# SpeakerEngine.net
KiCad netlist of a schematic drawn in Altium Designer
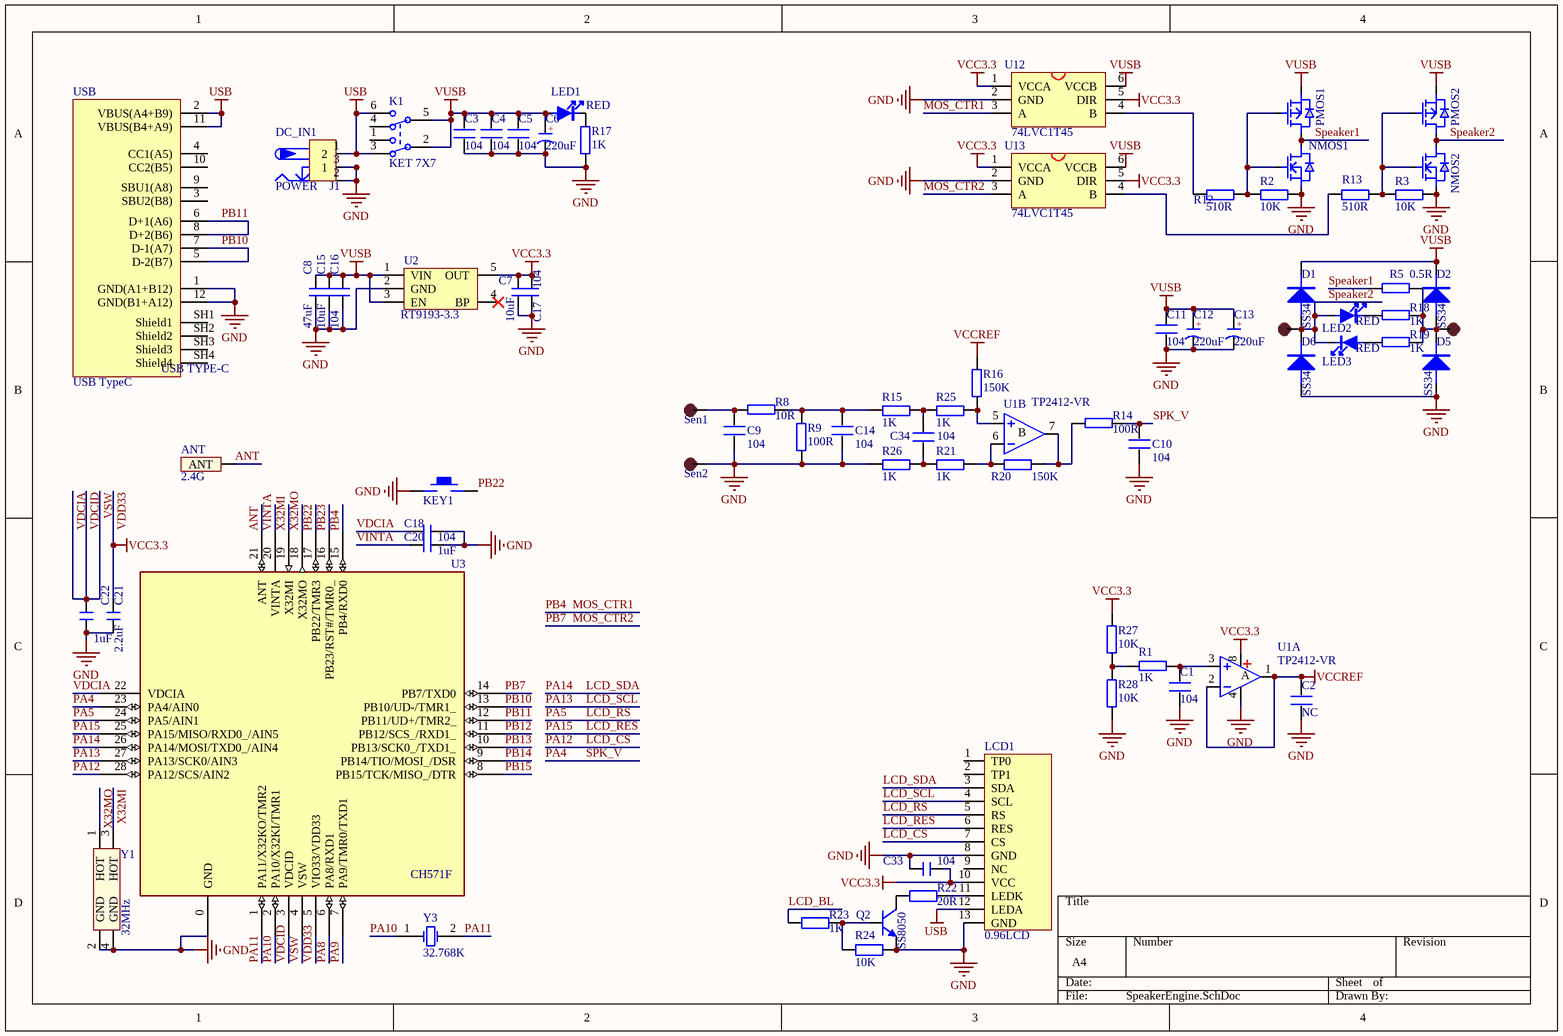
[diagram p0: SpeakerEngine.SchDoc]

(export (version "E")
  (design (tool "Eeschema 10.0.6"))
  (components
    (comp (ref "ANT")
      (value "2.4G")
      (footprint "2.4GANTS8")
      (description "2.4G天线")
      (libsource (lib "LovelessingSch") (part "ANT"))
    )
    (comp (ref "C1")
      (value "104")
      (footprint "C 0603_L")
      (libsource (lib "IMX6UL_ALPHA(底板)_V2.0") (part "C"))
    )
    (comp (ref "C2") (value "NC") (footprint "C 0603_L") (libsource (lib "IMX6UL_ALPHA(底板)_V2.0") (part "C")))
    (comp (ref "C3")
      (value "104")
      (footprint "C 0603_L")
      (libsource (lib "IMX6UL_ALPHA(底板)_V2.0") (part "C"))
    )
    (comp (ref "C4")
      (value "104")
      (footprint "C 0603_L")
      (libsource (lib "IMX6UL_ALPHA(底板)_V2.0") (part "C"))
    )
    (comp (ref "C5")
      (value "104")
      (footprint "C 0603_L")
      (libsource (lib "IMX6UL_ALPHA(底板)_V2.0") (part "C"))
    )
    (comp (ref "C6")
      (value "220uF")
      (footprint "CM D(6.3*5.4)")
      (description "有极性电容")
      (fields (field (name "版权归属") "正点原子"))
      (libsource (lib "正点原子封装库V1.0") (part "C-CAP"))
    )
    (comp (ref "C7")
      (value "10uF")
      (footprint "C 0603_L")
      (description "无极性贴片电容")
      (fields (field (name "版权归属") "正点原子"))
      (libsource (lib "电阻-电容-电感") (part "C"))
    )
    (comp (ref "C8")
      (value "47uF")
      (footprint "C 0603_L")
      (description "无极性贴片电容")
      (fields (field (name "版权归属") "正点原子"))
      (libsource (lib "电阻-电容-电感") (part "C"))
    )
    (comp (ref "C9")
      (value "104")
      (footprint "C 0603_L")
      (libsource (lib "IMX6UL_ALPHA(底板)_V2.0") (part "C"))
    )
    (comp (ref "C10")
      (value "104")
      (footprint "C 0603_L")
      (libsource (lib "IMX6UL_ALPHA(底板)_V2.0") (part "C"))
    )
    (comp (ref "C11")
      (value "104")
      (footprint "C 0603_L")
      (libsource (lib "IMX6UL_ALPHA(底板)_V2.0") (part "C"))
    )
    (comp (ref "C12")
      (value "220uF")
      (footprint "CM D(6.3*5.4)")
      (description "有极性电容")
      (fields (field (name "版权归属") "正点原子"))
      (libsource (lib "正点原子封装库V1.0") (part "C-CAP"))
    )
    (comp (ref "C13")
      (value "220uF")
      (footprint "CM D(6.3*5.4)")
      (description "有极性电容")
      (fields (field (name "版权归属") "正点原子"))
      (libsource (lib "正点原子封装库V1.0") (part "C-CAP"))
    )
    (comp (ref "C14")
      (value "104")
      (footprint "C 0603_L")
      (libsource (lib "IMX6UL_ALPHA(底板)_V2.0") (part "C"))
    )
    (comp (ref "C15")
      (value "10uF")
      (footprint "C 0603_L")
      (description "无极性贴片电容")
      (fields (field (name "版权归属") "正点原子"))
      (libsource (lib "电阻-电容-电感") (part "C"))
    )
    (comp (ref "C16")
      (value "104")
      (footprint "C 0603_L")
      (description "无极性贴片电容")
      (fields (field (name "版权归属") "正点原子"))
      (libsource (lib "电阻-电容-电感") (part "C"))
    )
    (comp (ref "C17")
      (value "104")
      (footprint "C 0603_L")
      (description "无极性贴片电容")
      (fields (field (name "版权归属") "正点原子"))
      (libsource (lib "电阻-电容-电感") (part "C"))
    )
    (comp (ref "C18")
      (value "104")
      (footprint "C 0603_L")
      (description "无极性贴片电容")
      (libsource (lib "LovelessingSch") (part "C"))
    )
    (comp (ref "C20")
      (value "1uF")
      (footprint "C 0603_L")
      (description "无极性贴片电容")
      (libsource (lib "LovelessingSch") (part "C"))
    )
    (comp (ref "C21")
      (value "2.2uF")
      (footprint "C 0603_L")
      (description "无极性贴片电容")
      (libsource (lib "LovelessingSch") (part "C"))
    )
    (comp (ref "C22")
      (value "1uF")
      (footprint "C 0603_L")
      (description "无极性贴片电容")
      (libsource (lib "LovelessingSch") (part "C"))
    )
    (comp (ref "C33")
      (value "104")
      (footprint "C 0603_L")
      (description "无极性电容")
      (fields (field (name "版权归属") "正点原子"))
      (libsource (lib "正点原子封装库V1.0") (part "C"))
    )
    (comp (ref "C34")
      (value "104")
      (footprint "C 0603_L")
      (libsource (lib "IMX6UL_ALPHA(底板)_V2.0") (part "C"))
    )
    (comp (ref "D1")
      (value "SS34")
      (footprint "SMA")
      (description "整流二极管")
      (libsource (lib "LovelessingSch") (part "DIODE"))
    )
    (comp (ref "D2")
      (value "SS34")
      (footprint "SMA")
      (description "整流二极管")
      (libsource (lib "LovelessingSch") (part "DIODE"))
    )
    (comp (ref "D5")
      (value "SS34")
      (footprint "SMA")
      (description "整流二极管")
      (libsource (lib "LovelessingSch") (part "DIODE"))
    )
    (comp (ref "D6")
      (value "SS34")
      (footprint "SMA")
      (description "整流二极管")
      (libsource (lib "LovelessingSch") (part "DIODE"))
    )
    (comp (ref "DC_IN1")
      (value "POWER")
      (footprint "DC-005")
      (description "低压电源接口")
      (fields (field (name "版权归属") "源创客"))
      (libsource (lib "IMX6UL_ALPHA(底板)_V2.0") (part "P-DC"))
    )
    (comp (ref "J1")
      (value "Header 1X2")
      (footprint "HDR2.54-LI-2P")
      (description "2P接插件")
      (fields (field (name "版权归属") "正点原子"))
      (libsource (lib "正点原子封装库V1.0") (part "Header 2"))
    )
    (comp (ref "K1")
      (value "KET 7X7")
      (footprint "KFT DIP-8X8")
      (description "7*7自锁开关")
      (fields (field (name "版权归属") "正点原子"))
      (libsource (lib "正点原子封装库V1.0") (part "KET 7X7"))
    )
    (comp (ref "KEY1")
      (value "KEY-SMD")
      (footprint "TSW SMD-3*6*2.5")
      (description "KEY,SMD,324225")
      (libsource (lib "Pandora_STM32L4_Board_V2.4") (part "S-KEY-SMD-324225"))
    )
    (comp (ref "LCD1")
      (value "0.96LCD")
      (footprint "LCD 0.96 13P")
      (description "0.96 LCD 80*160")
      (fields (field (name "版权归属") "正点原子"))
      (libsource (lib "正点原子封装库V1.0") (part "LCD 0.96"))
    )
    (comp (ref "LED1")
      (value "RED")
      (footprint "LED 0603B")
      (description "发光二极管")
      (libsource (lib "LovelessingSch") (part "LED"))
    )
    (comp (ref "LED2")
      (value "RED")
      (footprint "LED 0603B")
      (description "发光二极管")
      (libsource (lib "LovelessingSch") (part "LED"))
    )
    (comp (ref "LED3")
      (value "RED")
      (footprint "LED 0603B")
      (description "发光二极管")
      (libsource (lib "LovelessingSch") (part "LED"))
    )
    (comp (ref "NMOS1")
      (value "SI2302")
      (footprint "SOT23-3L")
      (description "SOT-23")
      (libsource (lib "LovelessingSch") (part "NMOS"))
    )
    (comp (ref "NMOS2")
      (value "SI2302")
      (footprint "SOT23-3L")
      (description "SOT-23")
      (libsource (lib "LovelessingSch") (part "NMOS"))
    )
    (comp (ref "PMOS1")
      (value "SI2301")
      (footprint "SOT23-3L")
      (description "SOT-23")
      (libsource (lib "LovelessingSch") (part "PMOS"))
    )
    (comp (ref "PMOS2")
      (value "SI2301")
      (footprint "SOT23-3L")
      (description "SOT-23")
      (libsource (lib "LovelessingSch") (part "PMOS"))
    )
    (comp (ref "Q2")
      (value "SS8050")
      (footprint "SOT23-3L")
      (description "高频放大-NPN型")
      (fields (field (name "版权归属") "正点原子"))
      (libsource (lib "正点原子封装库V1.0") (part "8050-SMD"))
    )
    (comp (ref "R1") (value "1K") (footprint "R 0603_L") (libsource (lib "IMX6UL_ALPHA(底板)_V2.0") (part "R")))
    (comp (ref "R2")
      (value "10K")
      (footprint "R 0603_L")
      (libsource (lib "IMX6UL_ALPHA(底板)_V2.0") (part "R"))
    )
    (comp (ref "R3")
      (value "10K")
      (footprint "R 0603_L")
      (libsource (lib "IMX6UL_ALPHA(底板)_V2.0") (part "R"))
    )
    (comp (ref "R5")
      (value "0.5R")
      (footprint "R 0805_L")
      (libsource (lib "IMX6UL_ALPHA(底板)_V2.0") (part "R"))
    )
    (comp (ref "R8")
      (value "10R")
      (footprint "R 0603_L")
      (libsource (lib "IMX6UL_ALPHA(底板)_V2.0") (part "R"))
    )
    (comp (ref "R9")
      (value "100R")
      (footprint "R 0603_L")
      (libsource (lib "IMX6UL_ALPHA(底板)_V2.0") (part "R"))
    )
    (comp (ref "R12")
      (value "510R")
      (footprint "R 0603_L")
      (libsource (lib "IMX6UL_ALPHA(底板)_V2.0") (part "R"))
    )
    (comp (ref "R13")
      (value "510R")
      (footprint "R 0603_L")
      (libsource (lib "IMX6UL_ALPHA(底板)_V2.0") (part "R"))
    )
    (comp (ref "R14")
      (value "100R")
      (footprint "R 0603_L")
      (libsource (lib "IMX6UL_ALPHA(底板)_V2.0") (part "R"))
    )
    (comp (ref "R15")
      (value "1K")
      (footprint "R 0603_L")
      (libsource (lib "IMX6UL_ALPHA(底板)_V2.0") (part "R"))
    )
    (comp (ref "R16")
      (value "150K")
      (footprint "R 0603_L")
      (libsource (lib "IMX6UL_ALPHA(底板)_V2.0") (part "R"))
    )
    (comp (ref "R17")
      (value "1K")
      (footprint "R 0603_L")
      (libsource (lib "IMX6UL_ALPHA(底板)_V2.0") (part "R"))
    )
    (comp (ref "R18")
      (value "1K")
      (footprint "R 0603_L")
      (libsource (lib "IMX6UL_ALPHA(底板)_V2.0") (part "R"))
    )
    (comp (ref "R19")
      (value "1K")
      (footprint "R 0603_L")
      (libsource (lib "IMX6UL_ALPHA(底板)_V2.0") (part "R"))
    )
    (comp (ref "R20")
      (value "150K")
      (footprint "R 0603_L")
      (libsource (lib "IMX6UL_ALPHA(底板)_V2.0") (part "R"))
    )
    (comp (ref "R21")
      (value "1K")
      (footprint "R 0603_L")
      (libsource (lib "IMX6UL_ALPHA(底板)_V2.0") (part "R"))
    )
    (comp (ref "R22")
      (value "20R")
      (footprint "R 0603_L")
      (description "贴片电阻")
      (libsource (lib "LovelessingSch") (part "R"))
    )
    (comp (ref "R23")
      (value "1K")
      (footprint "R 0603_L")
      (description "贴片电阻")
      (libsource (lib "LovelessingSch") (part "R"))
    )
    (comp (ref "R24")
      (value "10K")
      (footprint "R 0603_L")
      (description "贴片电阻")
      (libsource (lib "LovelessingSch") (part "R"))
    )
    (comp (ref "R25")
      (value "1K")
      (footprint "R 0603_L")
      (libsource (lib "IMX6UL_ALPHA(底板)_V2.0") (part "R"))
    )
    (comp (ref "R26")
      (value "1K")
      (footprint "R 0603_L")
      (libsource (lib "IMX6UL_ALPHA(底板)_V2.0") (part "R"))
    )
    (comp (ref "R27")
      (value "10K")
      (footprint "R 0603_L")
      (libsource (lib "IMX6UL_ALPHA(底板)_V2.0") (part "R"))
    )
    (comp (ref "R28")
      (value "10K")
      (footprint "R 0603_L")
      (libsource (lib "IMX6UL_ALPHA(底板)_V2.0") (part "R"))
    )
    (comp (ref "Sen1")
      (value "SPK+")
      (footprint "TP-1.5")
      (description "测试点")
      (libsource (lib "IMX6UL_ALPHA(底板)_V2.0") (part "TEST-POINT"))
    )
    (comp (ref "Sen2")
      (value "SPK+")
      (footprint "TP-1.5")
      (description "测试点")
      (libsource (lib "IMX6UL_ALPHA(底板)_V2.0") (part "TEST-POINT"))
    )
    (comp (ref "Speaker1")
      (value "SPK+")
      (footprint "TP-1.5")
      (description "测试点")
      (libsource (lib "IMX6UL_ALPHA(底板)_V2.0") (part "TEST-POINT"))
    )
    (comp (ref "Speaker2")
      (value "SPK+")
      (footprint "TP-1.5")
      (description "测试点")
      (libsource (lib "IMX6UL_ALPHA(底板)_V2.0") (part "TEST-POINT"))
    )
    (comp (ref "U1")
      (value "TP2412-VR")
      (footprint "SSOP8_N")
      (description "低压轨至轨双运放,5.5V 1MHz 4mV")
      (fields (field (name "版权归属") "正点原子"))
      (libsource (lib "正点原子封装库V1.0") (part "LMV358"))
    )
    (comp (ref "U2")
      (value "RT9193-3.3")
      (footprint "SOT23-5L")
      (description "LDO")
      (fields (field (name "版权归属") "正点原子"))
      (libsource (lib "LDO和DCDC") (part "LDO RT9193"))
    )
    (comp (ref "U3")
      (value "CH571F")
      (footprint "QFN28_4X4")
      (description "RISC-V MCU with BLE/USB/ADC/SPI/2*UART")
      (libsource (lib "LovelessingSch") (part "CH571F"))
    )
    (comp (ref "U12")
      (value "74LVC1T45")
      (footprint "SOT363-6L")
      (description "1路双向电平转换")
      (libsource (lib "LovelessingSch") (part "74LVC1T45"))
    )
    (comp (ref "U13")
      (value "74LVC1T45")
      (footprint "SOT363-6L")
      (description "1路双向电平转换")
      (libsource (lib "LovelessingSch") (part "74LVC1T45"))
    )
    (comp (ref "USB")
      (value "USB TypeC")
      (footprint "USB Type-C")
      (description "12P TypeC 母座")
      (fields (field (name "版权归属") "正点原子"))
      (libsource (lib "正点原子封装库V1.0") (part "USB 2.0 Type C"))
    )
    (comp (ref "Y1")
      (value "32MHz")
      (footprint "OSC 3225-4P")
      (description "晶振25MHz")
      (fields (field (name "PUBLISHER") "Altium Limited"))
      (libsource (lib "LovelessingSch") (part "Y-3225-4P"))
    )
    (comp (ref "Y3")
      (value "32.768K")
      (footprint "OSC 3215-2P")
      (description "晶振32.768K")
      (fields (field (name "PUBLISHER") "Altium Limited"))
      (libsource (lib "LovelessingSch") (part "Y-3215-2P"))
    )
  )
  (nets
    (net (code "1") (name "/ANT") (class "Default")
      (node (ref "ANT") (pin "1") (pinfunction "ANT_1") (pintype "passive"))
      (node (ref "U3") (pin "21") (pinfunction "ANT_21") (pintype "bidirectional"))
    )
    (net (code "2") (name "/LCD_BL") (class "Default")
      (node (ref "R23") (pin "1") (pinfunction "1_1") (pintype "passive"))
    )
    (net (code "3") (name "/LCD_CS") (class "Default")
      (node (ref "LCD1") (pin "7") (pinfunction "CS_7") (pintype "passive"))
      (node (ref "U3") (pin "28") (pinfunction "PA12/SCS/AIN2_28") (pintype "bidirectional"))
    )
    (net (code "4") (name "/LCD_RES") (class "Default")
      (node (ref "LCD1") (pin "6") (pinfunction "RES_6") (pintype "passive"))
      (node (ref "U3") (pin "25") (pinfunction "PA15/MISO/RXD0_/AIN5_25") (pintype "bidirectional"))
    )
    (net (code "5") (name "/LCD_RS") (class "Default")
      (node (ref "LCD1") (pin "5") (pinfunction "RS_5") (pintype "passive"))
      (node (ref "U3") (pin "24") (pinfunction "PA5/AIN1_24") (pintype "bidirectional"))
    )
    (net (code "6") (name "/LCD_SCL") (class "Default")
      (node (ref "LCD1") (pin "4") (pinfunction "SCL_4") (pintype "passive"))
      (node (ref "U3") (pin "27") (pinfunction "PA13/SCK0/AIN3_27") (pintype "bidirectional"))
    )
    (net (code "7") (name "/LCD_SDA") (class "Default")
      (node (ref "LCD1") (pin "3") (pinfunction "SDA_3") (pintype "passive"))
      (node (ref "U3") (pin "26") (pinfunction "PA14/MOSI/TXD0_/AIN4_26") (pintype "bidirectional"))
    )
    (net (code "8") (name "/MOS_CTR1") (class "Default")
      (node (ref "U12") (pin "3") (pinfunction "A_3") (pintype "passive"))
      (node (ref "U3") (pin "15") (pinfunction "PB4/RXD0_15") (pintype "bidirectional"))
    )
    (net (code "9") (name "/MOS_CTR2") (class "Default")
      (node (ref "U13") (pin "3") (pinfunction "A_3") (pintype "passive"))
      (node (ref "U3") (pin "14") (pinfunction "PB7/TXD0_14") (pintype "bidirectional"))
    )
    (net (code "10") (name "/PA4") (class "Default")
      (node (ref "C10") (pin "2") (pintype "passive"))
      (node (ref "R14") (pin "1") (pintype "passive"))
      (node (ref "U3") (pin "23") (pinfunction "PA4/AIN0_23") (pintype "bidirectional"))
    )
    (net (code "11") (name "/PA8") (class "Default")
      (node (ref "U3") (pin "6") (pinfunction "PA8/RXD1_6") (pintype "bidirectional"))
    )
    (net (code "12") (name "/PA9") (class "Default")
      (node (ref "U3") (pin "7") (pinfunction "PA9/TMR0/TXD1_7") (pintype "bidirectional"))
    )
    (net (code "13") (name "/PA10") (class "Default")
      (node (ref "U3") (pin "2") (pinfunction "PA10/X32KI/TMR1_2") (pintype "bidirectional"))
      (node (ref "Y3") (pin "1") (pinfunction "OSC1_1") (pintype "passive"))
    )
    (net (code "14") (name "/PA11") (class "Default")
      (node (ref "U3") (pin "1") (pinfunction "PA11/X32KO/TMR2_1") (pintype "bidirectional"))
      (node (ref "Y3") (pin "2") (pinfunction "OSC2_2") (pintype "passive"))
    )
    (net (code "15") (name "/PB10") (class "Default")
      (node (ref "U3") (pin "13") (pinfunction "PB10/UD-/TMR1__13") (pintype "bidirectional"))
      (node (ref "USB") (pin "5") (pinfunction "D-2(B7)_5") (pintype "passive"))
      (node (ref "USB") (pin "7") (pinfunction "D-1(A7)_7") (pintype "passive"))
    )
    (net (code "16") (name "/PB11") (class "Default")
      (node (ref "U3") (pin "12") (pinfunction "PB11/UD+/TMR2__12") (pintype "bidirectional"))
      (node (ref "USB") (pin "6") (pinfunction "D+1(A6)_6") (pintype "passive"))
      (node (ref "USB") (pin "8") (pinfunction "D+2(B6)_8") (pintype "passive"))
    )
    (net (code "17") (name "/PB12") (class "Default")
      (node (ref "U3") (pin "11") (pinfunction "PB12/SCS_/RXD1__11") (pintype "bidirectional"))
    )
    (net (code "18") (name "/PB13") (class "Default")
      (node (ref "U3") (pin "10") (pinfunction "PB13/SCK0_/TXD1__10") (pintype "bidirectional"))
    )
    (net (code "19") (name "/PB14") (class "Default")
      (node (ref "U3") (pin "9") (pinfunction "PB14/TIO/MOSI_/DSR_9") (pintype "bidirectional"))
    )
    (net (code "20") (name "/PB15") (class "Default")
      (node (ref "U3") (pin "8") (pinfunction "PB15/TCK/MISO_/DTR_8") (pintype "bidirectional"))
    )
    (net (code "21") (name "/PB22") (class "Default")
      (node (ref "KEY1") (pin "2") (pinfunction "2_2") (pintype "passive"))
      (node (ref "U3") (pin "17") (pinfunction "PB22/TMR3_17") (pintype "bidirectional"))
    )
    (net (code "22") (name "/PB23") (class "Default")
      (node (ref "U3") (pin "16") (pinfunction "PB23/RST#/TMR0__16") (pintype "bidirectional"))
    )
    (net (code "23") (name "/Speaker1") (class "Default")
      (node (ref "NMOS1") (pin "3") (pinfunction "D_3") (pintype "passive"))
      (node (ref "PMOS1") (pin "3") (pinfunction "D_3") (pintype "passive"))
      (node (ref "R5") (pin "2") (pintype "passive"))
    )
    (net (code "24") (name "/Speaker2") (class "Default")
      (node (ref "D1") (pin "1") (pinfunction "A_1") (pintype "passive"))
      (node (ref "D6") (pin "2") (pinfunction "K_2") (pintype "passive"))
      (node (ref "LED2") (pin "1") (pinfunction "1_1") (pintype "passive"))
      (node (ref "LED3") (pin "2") (pinfunction "2_2") (pintype "passive"))
      (node (ref "NMOS2") (pin "3") (pinfunction "D_3") (pintype "passive"))
      (node (ref "PMOS2") (pin "3") (pinfunction "D_3") (pintype "passive"))
      (node (ref "Speaker1") (pin "1") (pinfunction "1_1") (pintype "passive"))
    )
    (net (code "25") (name "/VDCIA") (class "Default")
      (node (ref "C18") (pin "1") (pinfunction "1_1") (pintype "passive"))
      (node (ref "C22") (pin "1") (pinfunction "1_1") (pintype "passive"))
      (node (ref "U3") (pin "22") (pinfunction "VDCIA_22") (pintype "power_in"))
      (node (ref "U3") (pin "3") (pinfunction "VDCID_3") (pintype "power_in"))
      (node (ref "U3") (pin "4") (pinfunction "VSW_4") (pintype "power_in"))
    )
    (net (code "26") (name "/VINTA") (class "Default")
      (node (ref "C20") (pin "1") (pinfunction "1_1") (pintype "passive"))
      (node (ref "U3") (pin "20") (pinfunction "VINTA_20") (pintype "power_in"))
    )
    (net (code "27") (name "/X32MI") (class "Default")
      (node (ref "U3") (pin "19") (pinfunction "X32MI_19") (pintype "input"))
      (node (ref "Y1") (pin "3") (pinfunction "HOT_3") (pintype "passive"))
    )
    (net (code "28") (name "/X32MO") (class "Default")
      (node (ref "U3") (pin "18") (pinfunction "X32MO_18") (pintype "output"))
      (node (ref "Y1") (pin "1") (pinfunction "HOT_1") (pintype "passive"))
    )
    (net (code "29") (name "GND") (class "Default")
      (node (ref "C1") (pin "1") (pintype "passive"))
      (node (ref "C10") (pin "1") (pintype "passive"))
      (node (ref "C11") (pin "1") (pintype "passive"))
      (node (ref "C12") (pin "2") (pinfunction "K_2") (pintype "passive"))
      (node (ref "C13") (pin "2") (pinfunction "K_2") (pintype "passive"))
      (node (ref "C14") (pin "1") (pintype "passive"))
      (node (ref "C15") (pin "2") (pinfunction "2_2") (pintype "passive"))
      (node (ref "C16") (pin "2") (pinfunction "2_2") (pintype "passive"))
      (node (ref "C17") (pin "2") (pinfunction "2_2") (pintype "passive"))
      (node (ref "C18") (pin "2") (pinfunction "2_2") (pintype "passive"))
      (node (ref "C2") (pin "1") (pintype "passive"))
      (node (ref "C20") (pin "2") (pinfunction "2_2") (pintype "passive"))
      (node (ref "C21") (pin "2") (pinfunction "2_2") (pintype "passive"))
      (node (ref "C22") (pin "2") (pinfunction "2_2") (pintype "passive"))
      (node (ref "C3") (pin "1") (pintype "passive"))
      (node (ref "C33") (pin "2") (pinfunction "2_2") (pintype "passive"))
      (node (ref "C4") (pin "1") (pintype "passive"))
      (node (ref "C5") (pin "1") (pintype "passive"))
      (node (ref "C6") (pin "2") (pinfunction "K_2") (pintype "passive"))
      (node (ref "C7") (pin "2") (pinfunction "2_2") (pintype "passive"))
      (node (ref "C8") (pin "2") (pinfunction "2_2") (pintype "passive"))
      (node (ref "C9") (pin "1") (pintype "passive"))
      (node (ref "D5") (pin "1") (pinfunction "A_1") (pintype "passive"))
      (node (ref "D6") (pin "1") (pinfunction "A_1") (pintype "passive"))
      (node (ref "DC_IN1") (pin "2") (pintype "power_in"))
      (node (ref "DC_IN1") (pin "3") (pintype "power_in"))
      (node (ref "J1") (pin "1") (pinfunction "1_1") (pintype "passive"))
      (node (ref "KEY1") (pin "1") (pinfunction "1_1") (pintype "passive"))
      (node (ref "LCD1") (pin "13") (pinfunction "GND_13") (pintype "passive"))
      (node (ref "LCD1") (pin "8") (pinfunction "GND_8") (pintype "passive"))
      (node (ref "NMOS1") (pin "2") (pinfunction "S_2") (pintype "passive"))
      (node (ref "NMOS2") (pin "2") (pinfunction "S_2") (pintype "passive"))
      (node (ref "Q2") (pin "2") (pinfunction "E_2") (pintype "passive"))
      (node (ref "R17") (pin "2") (pintype "passive"))
      (node (ref "R2") (pin "2") (pintype "passive"))
      (node (ref "R24") (pin "2") (pinfunction "2_2") (pintype "passive"))
      (node (ref "R26") (pin "1") (pintype "passive"))
      (node (ref "R28") (pin "2") (pintype "passive"))
      (node (ref "R3") (pin "2") (pintype "passive"))
      (node (ref "R9") (pin "2") (pintype "passive"))
      (node (ref "Sen2") (pin "1") (pinfunction "1_1") (pintype "passive"))
      (node (ref "U1") (pin "4") (pinfunction "V-_4") (pintype "passive"))
      (node (ref "U12") (pin "2") (pinfunction "GND_2") (pintype "passive"))
      (node (ref "U13") (pin "2") (pinfunction "GND_2") (pintype "passive"))
      (node (ref "U2") (pin "2") (pinfunction "GND_2") (pintype "passive"))
      (node (ref "U3") (pin "0") (pinfunction "GND_0") (pintype "power_in"))
      (node (ref "USB") (pin "1") (pinfunction "GND(A1+B12)_1") (pintype "passive"))
      (node (ref "USB") (pin "12") (pinfunction "GND(B1+A12)_12") (pintype "passive"))
      (node (ref "Y1") (pin "2") (pinfunction "GND_2") (pintype "passive"))
      (node (ref "Y1") (pin "4") (pinfunction "GND_4") (pintype "passive"))
    )
    (net (code "30") (name "Net-(C9-Pad2)") (class "Default")
      (node (ref "C9") (pin "2") (pintype "passive"))
      (node (ref "R8") (pin "2") (pintype "passive"))
      (node (ref "Sen1") (pin "1") (pinfunction "1_1") (pintype "passive"))
    )
    (net (code "31") (name "Net-(C14-Pad2)") (class "Default")
      (node (ref "C14") (pin "2") (pintype "passive"))
      (node (ref "R15") (pin "1") (pintype "passive"))
      (node (ref "R8") (pin "1") (pintype "passive"))
      (node (ref "R9") (pin "1") (pintype "passive"))
    )
    (net (code "32") (name "Net-(C34-Pad1)") (class "Default")
      (node (ref "C34") (pin "1") (pintype "passive"))
      (node (ref "R21") (pin "1") (pintype "passive"))
      (node (ref "R26") (pin "2") (pintype "passive"))
    )
    (net (code "33") (name "Net-(C34-Pad2)") (class "Default")
      (node (ref "C34") (pin "2") (pintype "passive"))
      (node (ref "R15") (pin "2") (pintype "passive"))
      (node (ref "R25") (pin "1") (pintype "passive"))
    )
    (net (code "34") (name "Net-(D2-A)") (class "Default")
      (node (ref "D2") (pin "1") (pinfunction "A_1") (pintype "passive"))
      (node (ref "D5") (pin "2") (pinfunction "K_2") (pintype "passive"))
      (node (ref "R18") (pin "1") (pintype "passive"))
      (node (ref "R19") (pin "1") (pintype "passive"))
      (node (ref "R5") (pin "1") (pintype "passive"))
      (node (ref "Speaker2") (pin "1") (pinfunction "1_1") (pintype "passive"))
    )
    (net (code "35") (name "Net-(LCD1-LEDK)") (class "Default")
      (node (ref "LCD1") (pin "11") (pinfunction "LEDK_11") (pintype "passive"))
      (node (ref "R22") (pin "2") (pinfunction "2_2") (pintype "passive"))
    )
    (net (code "36") (name "Net-(LED1-Pad2)") (class "Default")
      (node (ref "LED1") (pin "2") (pinfunction "2_2") (pintype "passive"))
      (node (ref "R17") (pin "1") (pintype "passive"))
    )
    (net (code "37") (name "Net-(LED2-Pad2)") (class "Default")
      (node (ref "LED2") (pin "2") (pinfunction "2_2") (pintype "passive"))
      (node (ref "R18") (pin "2") (pintype "passive"))
    )
    (net (code "38") (name "Net-(LED3-Pad1)") (class "Default")
      (node (ref "LED3") (pin "1") (pinfunction "1_1") (pintype "passive"))
      (node (ref "R19") (pin "2") (pintype "passive"))
    )
    (net (code "39") (name "Net-(NMOS1-G)") (class "Default")
      (node (ref "NMOS1") (pin "1") (pinfunction "G_1") (pintype "passive"))
      (node (ref "PMOS1") (pin "1") (pinfunction "G_1") (pintype "passive"))
      (node (ref "R12") (pin "2") (pintype "passive"))
      (node (ref "R2") (pin "1") (pintype "passive"))
    )
    (net (code "40") (name "Net-(NMOS2-G)") (class "Default")
      (node (ref "NMOS2") (pin "1") (pinfunction "G_1") (pintype "passive"))
      (node (ref "PMOS2") (pin "1") (pinfunction "G_1") (pintype "passive"))
      (node (ref "R13") (pin "2") (pintype "passive"))
      (node (ref "R3") (pin "1") (pintype "passive"))
    )
    (net (code "41") (name "Net-(Q2-B)") (class "Default")
      (node (ref "Q2") (pin "1") (pinfunction "B_1") (pintype "passive"))
      (node (ref "R23") (pin "2") (pinfunction "2_2") (pintype "passive"))
      (node (ref "R24") (pin "1") (pinfunction "1_1") (pintype "passive"))
    )
    (net (code "42") (name "Net-(Q2-C)") (class "Default")
      (node (ref "Q2") (pin "3") (pinfunction "C_3") (pintype "passive"))
      (node (ref "R22") (pin "1") (pinfunction "1_1") (pintype "passive"))
    )
    (net (code "43") (name "Net-(R1-Pad2)") (class "Default")
      (node (ref "R1") (pin "2") (pintype "passive"))
      (node (ref "R27") (pin "2") (pintype "passive"))
      (node (ref "R28") (pin "1") (pintype "passive"))
    )
    (net (code "44") (name "Net-(U1A-IN+)") (class "Default")
      (node (ref "C1") (pin "2") (pintype "passive"))
      (node (ref "R1") (pin "1") (pintype "passive"))
      (node (ref "U1") (pin "3") (pinfunction "IN+_3") (pintype "passive"))
    )
    (net (code "45") (name "Net-(U1B-IN+)") (class "Default")
      (node (ref "R16") (pin "2") (pintype "passive"))
      (node (ref "R25") (pin "2") (pintype "passive"))
      (node (ref "U1") (pin "5") (pinfunction "IN+_5") (pintype "passive"))
    )
    (net (code "46") (name "Net-(U1B-IN-)") (class "Default")
      (node (ref "R20") (pin "1") (pintype "passive"))
      (node (ref "R21") (pin "2") (pintype "passive"))
      (node (ref "U1") (pin "6") (pinfunction "IN-_6") (pintype "passive"))
    )
    (net (code "47") (name "Net-(U1B-OUT)") (class "Default")
      (node (ref "R14") (pin "2") (pintype "passive"))
      (node (ref "R20") (pin "2") (pintype "passive"))
      (node (ref "U1") (pin "7") (pinfunction "OUT_7") (pintype "passive"))
    )
    (net (code "48") (name "Net-(U12-B)") (class "Default")
      (node (ref "R12") (pin "1") (pintype "passive"))
      (node (ref "U12") (pin "4") (pinfunction "B_4") (pintype "passive"))
    )
    (net (code "49") (name "Net-(U13-B)") (class "Default")
      (node (ref "R13") (pin "1") (pintype "passive"))
      (node (ref "U13") (pin "4") (pinfunction "B_4") (pintype "passive"))
    )
    (net (code "50") (name "USB") (class "Default")
      (node (ref "DC_IN1") (pin "1") (pintype "power_in"))
      (node (ref "J1") (pin "2") (pinfunction "2_2") (pintype "passive"))
      (node (ref "K1") (pin "3") (pinfunction "NO1_3") (pintype "passive"))
      (node (ref "K1") (pin "6") (pinfunction "NC2_6") (pintype "passive"))
      (node (ref "LCD1") (pin "12") (pinfunction "LEDA_12") (pintype "passive"))
      (node (ref "USB") (pin "11") (pinfunction "VBUS(B4+A9)_11") (pintype "passive"))
      (node (ref "USB") (pin "2") (pinfunction "VBUS(A4+B9)_2") (pintype "passive"))
    )
    (net (code "51") (name "VCC3.3") (class "Default")
      (node (ref "C17") (pin "1") (pinfunction "1_1") (pintype "passive"))
      (node (ref "C21") (pin "1") (pinfunction "1_1") (pintype "passive"))
      (node (ref "C33") (pin "1") (pinfunction "1_1") (pintype "passive"))
      (node (ref "C7") (pin "1") (pinfunction "1_1") (pintype "passive"))
      (node (ref "LCD1") (pin "10") (pinfunction "VCC_10") (pintype "passive"))
      (node (ref "R27") (pin "1") (pintype "passive"))
      (node (ref "U1") (pin "8") (pinfunction "V+_8") (pintype "passive"))
      (node (ref "U12") (pin "1") (pinfunction "VCCA_1") (pintype "passive"))
      (node (ref "U12") (pin "5") (pinfunction "DIR_5") (pintype "passive"))
      (node (ref "U13") (pin "1") (pinfunction "VCCA_1") (pintype "passive"))
      (node (ref "U13") (pin "5") (pinfunction "DIR_5") (pintype "passive"))
      (node (ref "U2") (pin "5") (pinfunction "OUT_5") (pintype "passive"))
      (node (ref "U3") (pin "5") (pinfunction "VIO33/VDD33_5") (pintype "power_in"))
    )
    (net (code "52") (name "VCCREF") (class "Default")
      (node (ref "C2") (pin "2") (pintype "passive"))
      (node (ref "R16") (pin "1") (pintype "passive"))
      (node (ref "U1") (pin "1") (pinfunction "OUT_1") (pintype "passive"))
      (node (ref "U1") (pin "2") (pinfunction "IN-_2") (pintype "passive"))
    )
    (net (code "53") (name "VUSB") (class "Default")
      (node (ref "C11") (pin "2") (pintype "passive"))
      (node (ref "C12") (pin "1") (pinfunction "A_1") (pintype "passive"))
      (node (ref "C13") (pin "1") (pinfunction "A_1") (pintype "passive"))
      (node (ref "C15") (pin "1") (pinfunction "1_1") (pintype "passive"))
      (node (ref "C16") (pin "1") (pinfunction "1_1") (pintype "passive"))
      (node (ref "C3") (pin "2") (pintype "passive"))
      (node (ref "C4") (pin "2") (pintype "passive"))
      (node (ref "C5") (pin "2") (pintype "passive"))
      (node (ref "C6") (pin "1") (pinfunction "A_1") (pintype "passive"))
      (node (ref "C8") (pin "1") (pinfunction "1_1") (pintype "passive"))
      (node (ref "D1") (pin "2") (pinfunction "K_2") (pintype "passive"))
      (node (ref "D2") (pin "2") (pinfunction "K_2") (pintype "passive"))
      (node (ref "K1") (pin "2") (pinfunction "COM1_2") (pintype "passive"))
      (node (ref "K1") (pin "5") (pinfunction "COM2_5") (pintype "passive"))
      (node (ref "LED1") (pin "1") (pinfunction "1_1") (pintype "passive"))
      (node (ref "PMOS1") (pin "2") (pinfunction "S_2") (pintype "passive"))
      (node (ref "PMOS2") (pin "2") (pinfunction "S_2") (pintype "passive"))
      (node (ref "U12") (pin "6") (pinfunction "VCCB_6") (pintype "passive"))
      (node (ref "U13") (pin "6") (pinfunction "VCCB_6") (pintype "passive"))
      (node (ref "U2") (pin "1") (pinfunction "VIN_1") (pintype "passive"))
      (node (ref "U2") (pin "3") (pinfunction "EN_3") (pintype "passive"))
    )
    (net (code "54") (name "unconnected-(K1-NC1-Pad1)") (class "Default")
      (node (ref "K1") (pin "1") (pinfunction "NC1_1") (pintype "passive"))
    )
    (net (code "55") (name "unconnected-(K1-NO2-Pad4)") (class "Default")
      (node (ref "K1") (pin "4") (pinfunction "NO2_4") (pintype "passive"))
    )
    (net (code "56") (name "unconnected-(LCD1-NC-Pad9)") (class "Default")
      (node (ref "LCD1") (pin "9") (pinfunction "NC_9") (pintype "passive"))
    )
    (net (code "57") (name "unconnected-(LCD1-TP0-Pad1)") (class "Default")
      (node (ref "LCD1") (pin "1") (pinfunction "TP0_1") (pintype "passive"))
    )
    (net (code "58") (name "unconnected-(LCD1-TP1-Pad2)") (class "Default")
      (node (ref "LCD1") (pin "2") (pinfunction "TP1_2") (pintype "passive"))
    )
    (net (code "59") (name "unconnected-(U2-BP-Pad4)") (class "Default")
      (node (ref "U2") (pin "4") (pinfunction "BP_4") (pintype "passive+no_connect"))
    )
    (net (code "60") (name "unconnected-(USB-CC1(A5)-Pad4)") (class "Default")
      (node (ref "USB") (pin "4") (pinfunction "CC1(A5)_4") (pintype "passive"))
    )
    (net (code "61") (name "unconnected-(USB-CC2(B5)-Pad10)") (class "Default")
      (node (ref "USB") (pin "10") (pinfunction "CC2(B5)_10") (pintype "passive"))
    )
    (net (code "62") (name "unconnected-(USB-SBU1(A8)-Pad9)") (class "Default")
      (node (ref "USB") (pin "9") (pinfunction "SBU1(A8)_9") (pintype "passive"))
    )
    (net (code "63") (name "unconnected-(USB-SBU2(B8)-Pad3)") (class "Default")
      (node (ref "USB") (pin "3") (pinfunction "SBU2(B8)_3") (pintype "passive"))
    )
    (net (code "64") (name "unconnected-(USB-Shield1-PadSH1)") (class "Default")
      (node (ref "USB") (pin "SH1") (pinfunction "Shield1_SH1") (pintype "passive"))
    )
    (net (code "65") (name "unconnected-(USB-Shield2-PadSH2)") (class "Default")
      (node (ref "USB") (pin "SH2") (pinfunction "Shield2_SH2") (pintype "passive"))
    )
    (net (code "66") (name "unconnected-(USB-Shield3-PadSH3)") (class "Default")
      (node (ref "USB") (pin "SH3") (pinfunction "Shield3_SH3") (pintype "passive"))
    )
    (net (code "67") (name "unconnected-(USB-Shield4-PadSH4)") (class "Default")
      (node (ref "USB") (pin "SH4") (pinfunction "Shield4_SH4") (pintype "passive"))
    )
  )
)
